# max7219.net
KiCad netlist of a schematic drawn in EAGLE
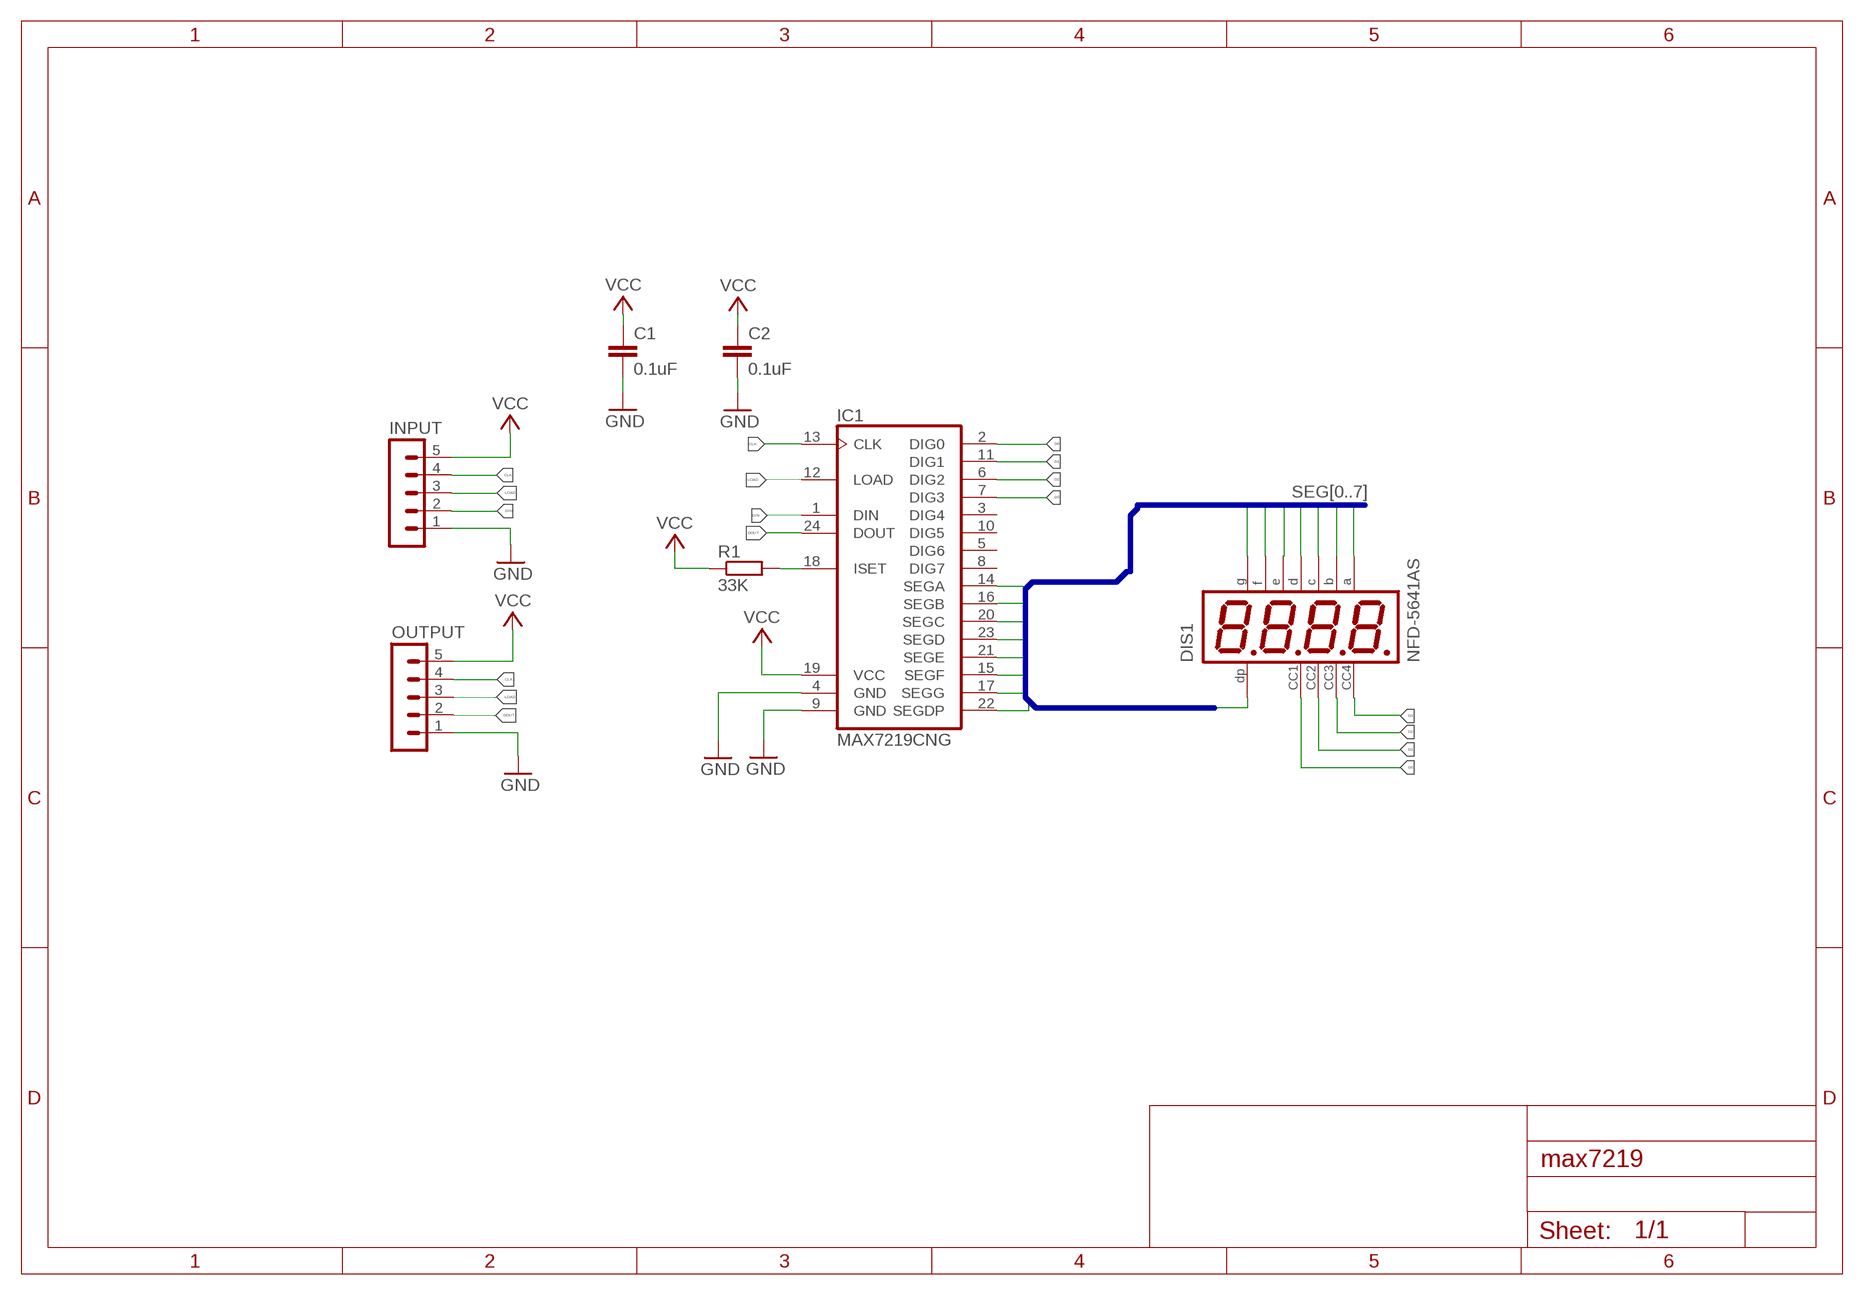
[diagram p0: schematic, sheet 1]

(export (version "E")
  (design (tool "Eeschema 10.0.6"))
  (components
    (comp (ref "C1")
      (value "0.1uF")
      (footprint "eagle-import:C025-025X050")
      (libsource (lib "eagle-import") (part "C-EU025-025X050"))
    )
    (comp (ref "C2")
      (value "0.1uF")
      (footprint "eagle-import:C025-025X050")
      (libsource (lib "eagle-import") (part "C-EU025-025X050"))
    )
    (comp (ref "DIS1")
      (value "NFD-5641AS")
      (footprint "eagle-import:NFD-5641")
      (libsource (lib "eagle-import") (part "NFD-5641AS"))
    )
    (comp (ref "IC1")
      (value "MAX7219CNG")
      (footprint "eagle-import:DIL24-3")
      (fields (field (name "MF") "MAXIM"))
      (libsource (lib "eagle-import") (part "MAX7219CNG"))
    )
    (comp (ref "INPUT")
      (value "MA05-1")
      (footprint "eagle-import:MA05-1")
      (libsource (lib "eagle-import") (part "MA05-1"))
    )
    (comp (ref "OUTPUT")
      (value "MA05-1")
      (footprint "eagle-import:MA05-1")
      (libsource (lib "eagle-import") (part "MA05-1"))
    )
    (comp (ref "R1")
      (value "33K")
      (footprint "eagle-import:0207_10")
      (libsource (lib "eagle-import") (part "R-EU_0207/10"))
    )
  )
  (nets
    (net (code "1") (name "/SEG0") (class "Default")
      (node (ref "DIS1") (pin "P$11") (pinfunction "P$11_P$11") (pintype "bidirectional"))
      (node (ref "IC1") (pin "14") (pinfunction "SEGA_14") (pintype "output"))
    )
    (net (code "2") (name "/SEG1") (class "Default")
      (node (ref "DIS1") (pin "P$7") (pinfunction "P$7_P$7") (pintype "bidirectional"))
      (node (ref "IC1") (pin "16") (pinfunction "SEGB_16") (pintype "output"))
    )
    (net (code "3") (name "/SEG2") (class "Default")
      (node (ref "DIS1") (pin "P$4") (pinfunction "P$4_P$4") (pintype "bidirectional"))
      (node (ref "IC1") (pin "20") (pinfunction "SEGC_20") (pintype "output"))
    )
    (net (code "4") (name "/SEG3") (class "Default")
      (node (ref "DIS1") (pin "P$2") (pinfunction "P$2_P$2") (pintype "bidirectional"))
      (node (ref "IC1") (pin "23") (pinfunction "SEGD_23") (pintype "output"))
    )
    (net (code "5") (name "/SEG4") (class "Default")
      (node (ref "DIS1") (pin "P$1") (pinfunction "P$1_P$1") (pintype "bidirectional"))
      (node (ref "IC1") (pin "21") (pinfunction "SEGE_21") (pintype "output"))
    )
    (net (code "6") (name "/SEG5") (class "Default")
      (node (ref "DIS1") (pin "P$10") (pinfunction "P$10_P$10") (pintype "bidirectional"))
      (node (ref "IC1") (pin "15") (pinfunction "SEGF_15") (pintype "output"))
    )
    (net (code "7") (name "/SEG6") (class "Default")
      (node (ref "DIS1") (pin "P$5") (pinfunction "P$5_P$5") (pintype "bidirectional"))
      (node (ref "IC1") (pin "17") (pinfunction "SEGG_17") (pintype "output"))
    )
    (net (code "8") (name "/SEG7") (class "Default")
      (node (ref "DIS1") (pin "P$3") (pinfunction "P$3_P$3") (pintype "bidirectional"))
      (node (ref "IC1") (pin "22") (pinfunction "SEGDP_22") (pintype "output"))
    )
    (net (code "10") (name "CLK") (class "Default")
      (node (ref "IC1") (pin "13") (pinfunction "CLK_13") (pintype "input"))
      (node (ref "INPUT") (pin "4") (pinfunction "4_4") (pintype "passive"))
      (node (ref "OUTPUT") (pin "4") (pinfunction "4_4") (pintype "passive"))
    )
    (net (code "11") (name "D0") (class "Default")
      (node (ref "DIS1") (pin "P$12") (pinfunction "P$12_P$12") (pintype "bidirectional"))
      (node (ref "IC1") (pin "2") (pinfunction "DIG0_2") (pintype "output"))
    )
    (net (code "12") (name "D1") (class "Default")
      (node (ref "DIS1") (pin "P$9") (pinfunction "P$9_P$9") (pintype "bidirectional"))
      (node (ref "IC1") (pin "11") (pinfunction "DIG1_11") (pintype "output"))
    )
    (net (code "13") (name "D2") (class "Default")
      (node (ref "DIS1") (pin "P$8") (pinfunction "P$8_P$8") (pintype "bidirectional"))
      (node (ref "IC1") (pin "6") (pinfunction "DIG2_6") (pintype "output"))
    )
    (net (code "14") (name "D3") (class "Default")
      (node (ref "DIS1") (pin "P$6") (pinfunction "P$6_P$6") (pintype "bidirectional"))
      (node (ref "IC1") (pin "7") (pinfunction "DIG3_7") (pintype "output"))
    )
    (net (code "15") (name "DIN") (class "Default")
      (node (ref "IC1") (pin "1") (pinfunction "DIN_1") (pintype "input"))
      (node (ref "INPUT") (pin "2") (pinfunction "2_2") (pintype "passive"))
    )
    (net (code "16") (name "DOUT") (class "Default")
      (node (ref "IC1") (pin "24") (pinfunction "DOUT_24") (pintype "output"))
      (node (ref "OUTPUT") (pin "2") (pinfunction "2_2") (pintype "passive"))
    )
    (net (code "17") (name "GND") (class "Default")
      (node (ref "C1") (pin "2") (pinfunction "2_2") (pintype "passive"))
      (node (ref "C2") (pin "2") (pinfunction "2_2") (pintype "passive"))
      (node (ref "IC1") (pin "4") (pinfunction "GND_4") (pintype "power_in"))
      (node (ref "IC1") (pin "9") (pinfunction "GND_9") (pintype "power_in"))
      (node (ref "INPUT") (pin "1") (pinfunction "1_1") (pintype "passive"))
      (node (ref "OUTPUT") (pin "1") (pinfunction "1_1") (pintype "passive"))
    )
    (net (code "18") (name "LOAD") (class "Default")
      (node (ref "IC1") (pin "12") (pinfunction "LOAD_12") (pintype "input"))
      (node (ref "INPUT") (pin "3") (pinfunction "3_3") (pintype "passive"))
      (node (ref "OUTPUT") (pin "3") (pinfunction "3_3") (pintype "passive"))
    )
    (net (code "19") (name "Net-(IC1-ISET)") (class "Default")
      (node (ref "IC1") (pin "18") (pinfunction "ISET_18") (pintype "input"))
      (node (ref "R1") (pin "2") (pinfunction "2_2") (pintype "passive"))
    )
    (net (code "20") (name "VCC") (class "Default")
      (node (ref "C1") (pin "1") (pinfunction "1_1") (pintype "passive"))
      (node (ref "C2") (pin "1") (pinfunction "1_1") (pintype "passive"))
      (node (ref "IC1") (pin "19") (pinfunction "VCC_19") (pintype "power_in"))
      (node (ref "INPUT") (pin "5") (pinfunction "5_5") (pintype "passive"))
      (node (ref "OUTPUT") (pin "5") (pinfunction "5_5") (pintype "passive"))
      (node (ref "R1") (pin "1") (pinfunction "1_1") (pintype "passive"))
    )
    (net (code "21") (name "unconnected-(IC1-DIG4-Pad3)") (class "Default")
      (node (ref "IC1") (pin "3") (pinfunction "DIG4_3") (pintype "output"))
    )
    (net (code "22") (name "unconnected-(IC1-DIG5-Pad10)") (class "Default")
      (node (ref "IC1") (pin "10") (pinfunction "DIG5_10") (pintype "output"))
    )
    (net (code "23") (name "unconnected-(IC1-DIG6-Pad5)") (class "Default")
      (node (ref "IC1") (pin "5") (pinfunction "DIG6_5") (pintype "output"))
    )
    (net (code "24") (name "unconnected-(IC1-DIG7-Pad8)") (class "Default")
      (node (ref "IC1") (pin "8") (pinfunction "DIG7_8") (pintype "output"))
    )
  )
)
